# Button.net
KiCad netlist of a schematic drawn in EAGLE
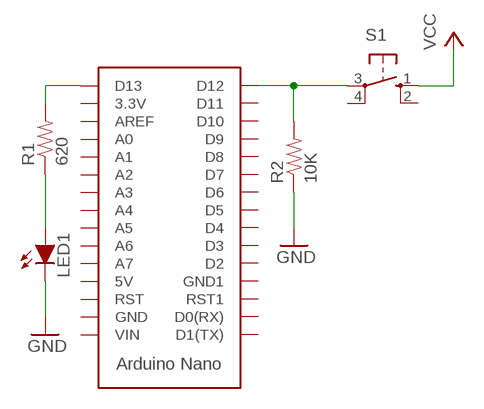
[diagram p0: schematic, sheet 1]

(export (version "E")
  (design (tool "Eeschema 10.0.6"))
  (components
    (comp (ref "LED1")
      (value "LED-3MM")
      (footprint "eagle-import:LED-3MM")
      (libsource (lib "eagle-import") (part "LED-3MM"))
    )
    (comp (ref "R1")
      (value "620")
      (footprint "eagle-import:10W_RESISTOR_VISHAY")
      (libsource (lib "eagle-import") (part "RESISTOR10W"))
    )
    (comp (ref "R2")
      (value "10K")
      (footprint "eagle-import:10W_RESISTOR_VISHAY")
      (libsource (lib "eagle-import") (part "RESISTOR10W"))
    )
    (comp (ref "S1")
      (value "BTN_10-XX")
      (footprint "eagle-import:B3F-10XX")
      (fields (field (name "MPN") "B3F-1000"))
      (libsource (lib "eagle-import") (part "BTN_10-XX"))
    )
    (comp (ref "U$1")
      (value "ARDUINO_NANO")
      (footprint "eagle-import:ARDUINO_NANO")
      (libsource (lib "eagle-import") (part "ARDUINO_NANO"))
    )
  )
  (nets
    (net (code "1") (name "GND") (class "Default")
      (node (ref "LED1") (pin "K") (pinfunction "C_K") (pintype "passive"))
      (node (ref "R2") (pin "1") (pinfunction "1_1") (pintype "passive"))
    )
    (net (code "2") (name "Net-(LED1-PadA)") (class "Default")
      (node (ref "LED1") (pin "A") (pinfunction "A_A") (pintype "passive"))
      (node (ref "R1") (pin "1") (pinfunction "1_1") (pintype "passive"))
    )
    (net (code "3") (name "Net-(R1-Pad2)") (class "Default")
      (node (ref "R1") (pin "2") (pinfunction "2_2") (pintype "passive"))
      (node (ref "U$1") (pin "D13") (pinfunction "D13_D13") (pintype "bidirectional"))
    )
    (net (code "4") (name "Net-(S1-P)") (class "Default")
      (node (ref "R2") (pin "2") (pinfunction "2_2") (pintype "passive"))
      (node (ref "S1") (pin "3") (pinfunction "P_3") (pintype "passive"))
      (node (ref "U$1") (pin "D12") (pinfunction "D12_D12") (pintype "bidirectional"))
    )
    (net (code "5") (name "VCC") (class "Default")
      (node (ref "S1") (pin "1") (pinfunction "S_1") (pintype "passive"))
    )
    (net (code "6") (name "unconnected-(S1-P1-Pad4)") (class "Default")
      (node (ref "S1") (pin "4") (pinfunction "P1_4") (pintype "passive"))
    )
    (net (code "7") (name "unconnected-(S1-S1-Pad2)") (class "Default")
      (node (ref "S1") (pin "2") (pinfunction "S1_2") (pintype "passive"))
    )
    (net (code "8") (name "unconnected-(U$1-Pad3.3V)") (class "Default")
      (node (ref "U$1") (pin "3.3V") (pinfunction "3.3V_3.3V") (pintype "bidirectional"))
    )
    (net (code "9") (name "unconnected-(U$1-Pad5V)") (class "Default")
      (node (ref "U$1") (pin "5V") (pinfunction "5V_5V") (pintype "bidirectional"))
    )
    (net (code "10") (name "unconnected-(U$1-PadA0)") (class "Default")
      (node (ref "U$1") (pin "A0") (pinfunction "A0_A0") (pintype "bidirectional"))
    )
    (net (code "11") (name "unconnected-(U$1-PadA1)") (class "Default")
      (node (ref "U$1") (pin "A1") (pinfunction "A1_A1") (pintype "bidirectional"))
    )
    (net (code "12") (name "unconnected-(U$1-PadA2)") (class "Default")
      (node (ref "U$1") (pin "A2") (pinfunction "A2_A2") (pintype "bidirectional"))
    )
    (net (code "13") (name "unconnected-(U$1-PadA3)") (class "Default")
      (node (ref "U$1") (pin "A3") (pinfunction "A3_A3") (pintype "bidirectional"))
    )
    (net (code "14") (name "unconnected-(U$1-PadA4)") (class "Default")
      (node (ref "U$1") (pin "A4") (pinfunction "A4_A4") (pintype "bidirectional"))
    )
    (net (code "15") (name "unconnected-(U$1-PadA5)") (class "Default")
      (node (ref "U$1") (pin "A5") (pinfunction "A5_A5") (pintype "bidirectional"))
    )
    (net (code "16") (name "unconnected-(U$1-PadA6)") (class "Default")
      (node (ref "U$1") (pin "A6") (pinfunction "A6_A6") (pintype "bidirectional"))
    )
    (net (code "17") (name "unconnected-(U$1-PadA7)") (class "Default")
      (node (ref "U$1") (pin "A7") (pinfunction "A7_A7") (pintype "bidirectional"))
    )
    (net (code "18") (name "unconnected-(U$1-PadAREF)") (class "Default")
      (node (ref "U$1") (pin "AREF") (pinfunction "AREF_AREF") (pintype "bidirectional"))
    )
    (net (code "19") (name "unconnected-(U$1-PadD0(RX))") (class "Default")
      (node (ref "U$1") (pin "D0(RX)") (pinfunction "D0(RX)_D0(RX)") (pintype "bidirectional"))
    )
    (net (code "20") (name "unconnected-(U$1-PadD1(TX))") (class "Default")
      (node (ref "U$1") (pin "D1(TX)") (pinfunction "D1(TX)_D1(TX)") (pintype "bidirectional"))
    )
    (net (code "21") (name "unconnected-(U$1-PadD2)") (class "Default")
      (node (ref "U$1") (pin "D2") (pinfunction "D2_D2") (pintype "bidirectional"))
    )
    (net (code "22") (name "unconnected-(U$1-PadD3)") (class "Default")
      (node (ref "U$1") (pin "D3") (pinfunction "D3_D3") (pintype "bidirectional"))
    )
    (net (code "23") (name "unconnected-(U$1-PadD4)") (class "Default")
      (node (ref "U$1") (pin "D4") (pinfunction "D4_D4") (pintype "bidirectional"))
    )
    (net (code "24") (name "unconnected-(U$1-PadD5)") (class "Default")
      (node (ref "U$1") (pin "D5") (pinfunction "D5_D5") (pintype "bidirectional"))
    )
    (net (code "25") (name "unconnected-(U$1-PadD6)") (class "Default")
      (node (ref "U$1") (pin "D6") (pinfunction "D6_D6") (pintype "bidirectional"))
    )
    (net (code "26") (name "unconnected-(U$1-PadD7)") (class "Default")
      (node (ref "U$1") (pin "D7") (pinfunction "D7_D7") (pintype "bidirectional"))
    )
    (net (code "27") (name "unconnected-(U$1-PadD8)") (class "Default")
      (node (ref "U$1") (pin "D8") (pinfunction "D8_D8") (pintype "bidirectional"))
    )
    (net (code "28") (name "unconnected-(U$1-PadD9)") (class "Default")
      (node (ref "U$1") (pin "D9") (pinfunction "D9_D9") (pintype "bidirectional"))
    )
    (net (code "29") (name "unconnected-(U$1-PadD10)") (class "Default")
      (node (ref "U$1") (pin "D10") (pinfunction "D10_D10") (pintype "bidirectional"))
    )
    (net (code "30") (name "unconnected-(U$1-PadD11)") (class "Default")
      (node (ref "U$1") (pin "D11") (pinfunction "D11_D11") (pintype "bidirectional"))
    )
    (net (code "31") (name "unconnected-(U$1-PadGND)") (class "Default")
      (node (ref "U$1") (pin "GND") (pinfunction "GND_GND") (pintype "bidirectional"))
    )
    (net (code "32") (name "unconnected-(U$1-PadGND1)") (class "Default")
      (node (ref "U$1") (pin "GND1") (pinfunction "GND1_GND1") (pintype "bidirectional"))
    )
    (net (code "33") (name "unconnected-(U$1-PadRST)") (class "Default")
      (node (ref "U$1") (pin "RST") (pinfunction "RST_RST") (pintype "bidirectional"))
    )
    (net (code "34") (name "unconnected-(U$1-PadRST1)") (class "Default")
      (node (ref "U$1") (pin "RST1") (pinfunction "RST1_RST1") (pintype "bidirectional"))
    )
    (net (code "35") (name "unconnected-(U$1-PadVIN)") (class "Default")
      (node (ref "U$1") (pin "VIN") (pinfunction "VIN_VIN") (pintype "bidirectional"))
    )
  )
)
